# EEM_Connectors.net
KiCad netlist of a schematic drawn in Altium Designer
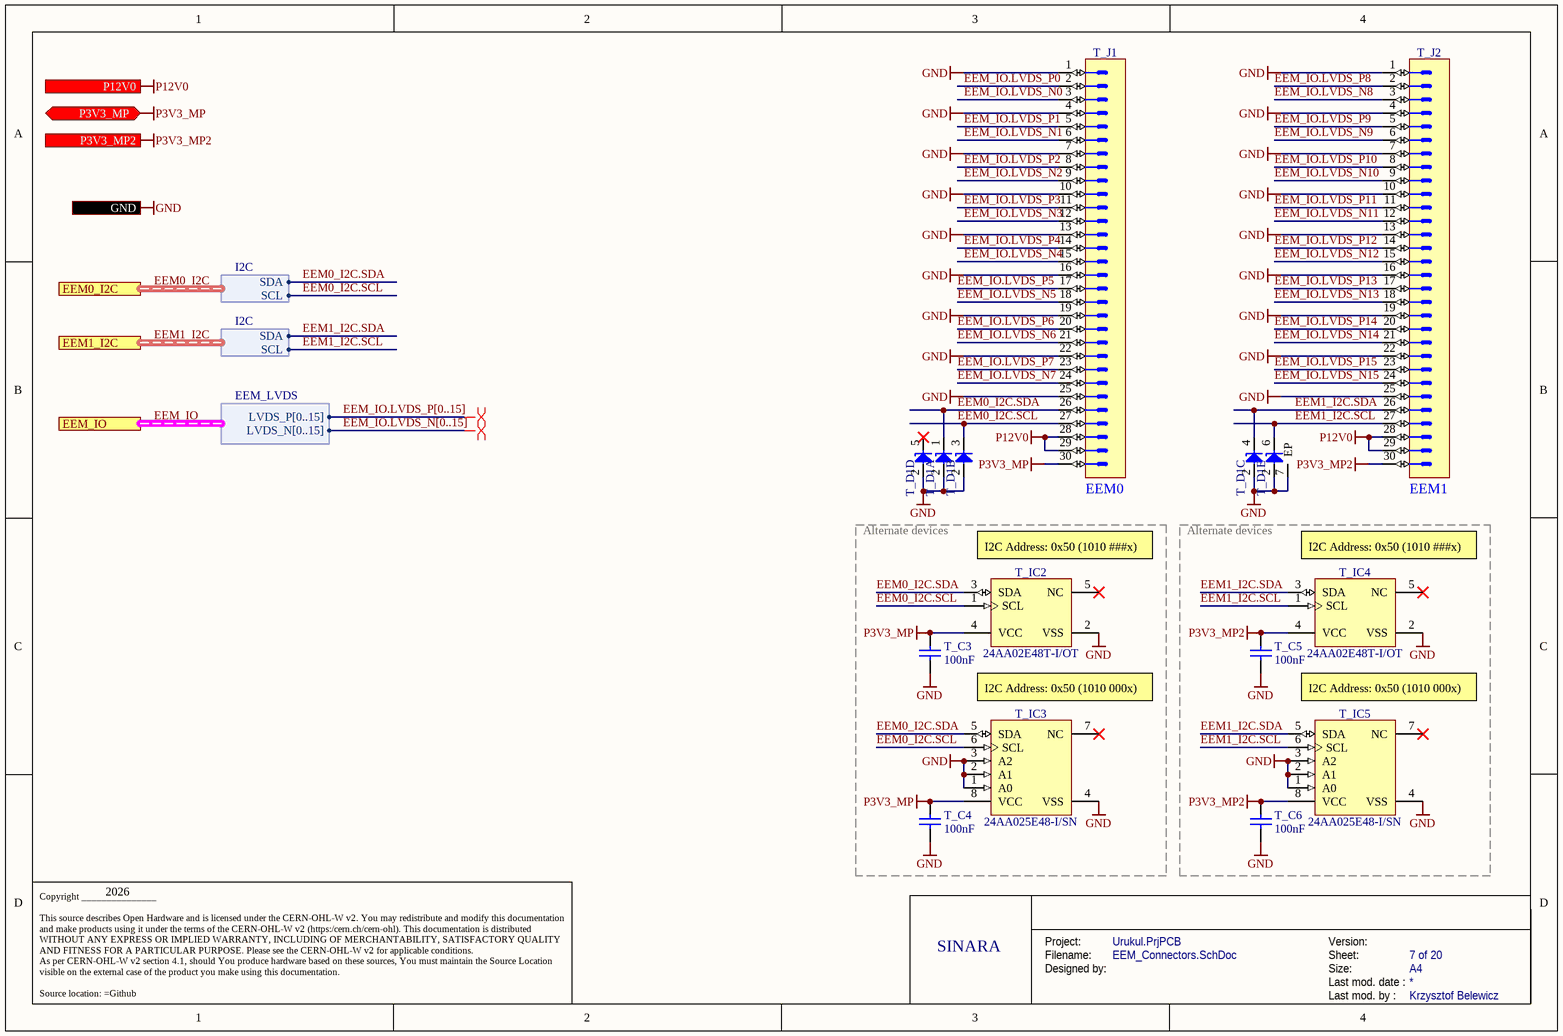
[diagram p0: EEM_Connectors.SchDoc]

(export (version "E")
  (design (tool "Eeschema 10.0.6"))
  (components
    (comp (ref "T_C3")
      (value "100nF")
      (footprint "CAPC1005X55N")
      (description "Non-polarised capacitor")
      (fields
        (field (name "PART NUMBER") "CC0402_100NF_16V_10%_X5R")
        (field (name "VOLTAGE") "16V")
        (field (name "AUTHOR") "CERN DEM JLC")
      )
      (libsource (lib "Capacitors") (part "Capacitor - non polarized"))
    )
    (comp (ref "T_C4")
      (value "100nF")
      (footprint "CAPC1005X55N")
      (description "Non-polarised capacitor")
      (fields
        (field (name "PART NUMBER") "CC0402_100NF_16V_10%_X5R")
        (field (name "VOLTAGE") "16V")
        (field (name "AUTHOR") "CERN DEM JLC")
      )
      (libsource (lib "Capacitors") (part "Capacitor - non polarized"))
    )
    (comp (ref "T_C5")
      (value "100nF")
      (footprint "CAPC1005X55N")
      (description "Non-polarised capacitor")
      (fields
        (field (name "PART NUMBER") "CC0402_100NF_16V_10%_X5R")
        (field (name "VOLTAGE") "16V")
        (field (name "AUTHOR") "CERN DEM JLC")
      )
      (libsource (lib "Capacitors") (part "Capacitor - non polarized"))
    )
    (comp (ref "T_C6")
      (value "100nF")
      (footprint "CAPC1005X55N")
      (description "Non-polarised capacitor")
      (fields
        (field (name "PART NUMBER") "CC0402_100NF_16V_10%_X5R")
        (field (name "VOLTAGE") "16V")
        (field (name "AUTHOR") "CERN DEM JLC")
      )
      (libsource (lib "Capacitors") (part "Capacitor - non polarized"))
    )
    (comp (ref "T_D1")
      (value "UCLAMP3305P.TCT")
      (footprint "SON50P160X65_HS-7N")
      (description "Diode TVS Quint Common Anode Uni-Dir 3.3V 40W 6-Pin SLP EP T/R")
      (libsource (lib "TechnoSystem Workspace") (part "D-AK-2"))
    )
    (comp (ref "T_IC2")
      (value "24AA02E48T-I/OT")
      (footprint "SOT95P280X145-5N")
      (description "1.7V-5.5V, 2K I2C Serial EEPROM With EUI-48 Node Identity")
      (fields (field (name "MANUFACTURER") "MICROCHIP TECHNOLOGY") (field (name "AUTHOR") "CERN DEM MR"))
      (libsource (lib "ICs And Semiconductors") (part "24AA02E48T-I/OT"))
    )
    (comp (ref "T_IC3")
      (value "24AA025E48-I/SN")
      (footprint "SOIC127P600X175-8N")
      (description "1.7V-5.5V, 2K I2C™ Serial EEPROMs with EUI-48™ Node Identity")
      (fields (field (name "MANUFACTURER") "MICROCHIP TECHNOLOGY") (field (name "AUTHOR") "CERN DEM MR"))
      (libsource (lib "ICs And Semiconductors") (part "24AA025E48-I/SN"))
    )
    (comp (ref "T_IC4")
      (value "24AA02E48T-I/OT")
      (footprint "SOT95P280X145-5N")
      (description "1.7V-5.5V, 2K I2C Serial EEPROM With EUI-48 Node Identity")
      (fields (field (name "MANUFACTURER") "MICROCHIP TECHNOLOGY") (field (name "AUTHOR") "CERN DEM MR"))
      (libsource (lib "ICs And Semiconductors") (part "24AA02E48T-I/OT"))
    )
    (comp (ref "T_IC5")
      (value "24AA025E48-I/SN")
      (footprint "SOIC127P600X175-8N")
      (description "1.7V-5.5V, 2K I2C™ Serial EEPROMs with EUI-48™ Node Identity")
      (fields (field (name "MANUFACTURER") "MICROCHIP TECHNOLOGY") (field (name "AUTHOR") "CERN DEM MR"))
      (libsource (lib "ICs And Semiconductors") (part "24AA025E48-I/SN"))
    )
    (comp (ref "T_J1")
      (value "~")
      (footprint "3M_N2530-6002RB")
      (description "Connector 30 Male")
      (fields
        (field (name "PART NUMBER") "3M_N2530-6002RB")
        (field (name "MANUFACTURER") "3M")
        (field (name "AUTHOR") "CERN DEM JLC")
      )
      (libsource (lib "Connectors") (part "Connector 30 Male"))
    )
    (comp (ref "T_J2")
      (value "~")
      (footprint "3M_N2530-6002RB")
      (description "Connector 30 Male")
      (fields
        (field (name "PART NUMBER") "3M_N2530-6002RB")
        (field (name "MANUFACTURER") "3M")
        (field (name "AUTHOR") "CERN DEM JLC")
      )
      (libsource (lib "Connectors") (part "Connector 30 Male"))
    )
  )
  (nets
    (net (code "4") (name "/EEM0_I2C.SCL") (class "Default")
      (node (ref "T_D1") (pin "3") (pinfunction "C_3") (pintype "passive"))
      (node (ref "T_IC2") (pin "1") (pinfunction "SCL_1") (pintype "input"))
      (node (ref "T_IC3") (pin "6") (pinfunction "SCL_6") (pintype "input"))
      (node (ref "T_J1") (pin "27") (pinfunction "27_27") (pintype "bidirectional"))
    )
    (net (code "5") (name "/EEM0_I2C.SDA") (class "Default")
      (node (ref "T_D1") (pin "1") (pinfunction "C_1") (pintype "passive"))
      (node (ref "T_IC2") (pin "3") (pinfunction "SDA_3") (pintype "bidirectional"))
      (node (ref "T_IC3") (pin "5") (pinfunction "SDA_5") (pintype "bidirectional"))
      (node (ref "T_J1") (pin "26") (pinfunction "26_26") (pintype "bidirectional"))
    )
    (net (code "7") (name "/EEM1_I2C.SCL") (class "Default")
      (node (ref "T_D1") (pin "6") (pinfunction "C_6") (pintype "passive"))
      (node (ref "T_IC4") (pin "1") (pinfunction "SCL_1") (pintype "input"))
      (node (ref "T_IC5") (pin "6") (pinfunction "SCL_6") (pintype "input"))
      (node (ref "T_J2") (pin "27") (pinfunction "27_27") (pintype "bidirectional"))
    )
    (net (code "8") (name "/EEM1_I2C.SDA") (class "Default")
      (node (ref "T_D1") (pin "4") (pinfunction "C_4") (pintype "passive"))
      (node (ref "T_IC4") (pin "3") (pinfunction "SDA_3") (pintype "bidirectional"))
      (node (ref "T_IC5") (pin "5") (pinfunction "SDA_5") (pintype "bidirectional"))
      (node (ref "T_J2") (pin "26") (pinfunction "26_26") (pintype "bidirectional"))
    )
    (net (code "10") (name "/EEM_IO.LVDS_N0") (class "Default")
      (node (ref "T_J1") (pin "3") (pinfunction "3_3") (pintype "bidirectional"))
    )
    (net (code "11") (name "/EEM_IO.LVDS_N1") (class "Default")
      (node (ref "T_J1") (pin "6") (pinfunction "6_6") (pintype "bidirectional"))
    )
    (net (code "12") (name "/EEM_IO.LVDS_N2") (class "Default")
      (node (ref "T_J1") (pin "9") (pinfunction "9_9") (pintype "bidirectional"))
    )
    (net (code "13") (name "/EEM_IO.LVDS_N3") (class "Default")
      (node (ref "T_J1") (pin "12") (pinfunction "12_12") (pintype "bidirectional"))
    )
    (net (code "14") (name "/EEM_IO.LVDS_N4") (class "Default")
      (node (ref "T_J1") (pin "15") (pinfunction "15_15") (pintype "bidirectional"))
    )
    (net (code "15") (name "/EEM_IO.LVDS_N5") (class "Default")
      (node (ref "T_J1") (pin "18") (pinfunction "18_18") (pintype "bidirectional"))
    )
    (net (code "16") (name "/EEM_IO.LVDS_N6") (class "Default")
      (node (ref "T_J1") (pin "21") (pinfunction "21_21") (pintype "bidirectional"))
    )
    (net (code "17") (name "/EEM_IO.LVDS_N7") (class "Default")
      (node (ref "T_J1") (pin "24") (pinfunction "24_24") (pintype "bidirectional"))
    )
    (net (code "18") (name "/EEM_IO.LVDS_N8") (class "Default")
      (node (ref "T_J2") (pin "3") (pinfunction "3_3") (pintype "bidirectional"))
    )
    (net (code "19") (name "/EEM_IO.LVDS_N9") (class "Default")
      (node (ref "T_J2") (pin "6") (pinfunction "6_6") (pintype "bidirectional"))
    )
    (net (code "20") (name "/EEM_IO.LVDS_N10") (class "Default")
      (node (ref "T_J2") (pin "9") (pinfunction "9_9") (pintype "bidirectional"))
    )
    (net (code "21") (name "/EEM_IO.LVDS_N11") (class "Default")
      (node (ref "T_J2") (pin "12") (pinfunction "12_12") (pintype "bidirectional"))
    )
    (net (code "22") (name "/EEM_IO.LVDS_N12") (class "Default")
      (node (ref "T_J2") (pin "15") (pinfunction "15_15") (pintype "bidirectional"))
    )
    (net (code "23") (name "/EEM_IO.LVDS_N13") (class "Default")
      (node (ref "T_J2") (pin "18") (pinfunction "18_18") (pintype "bidirectional"))
    )
    (net (code "24") (name "/EEM_IO.LVDS_N14") (class "Default")
      (node (ref "T_J2") (pin "21") (pinfunction "21_21") (pintype "bidirectional"))
    )
    (net (code "25") (name "/EEM_IO.LVDS_N15") (class "Default")
      (node (ref "T_J2") (pin "24") (pinfunction "24_24") (pintype "bidirectional"))
    )
    (net (code "27") (name "/EEM_IO.LVDS_P0") (class "Default")
      (node (ref "T_J1") (pin "2") (pinfunction "2_2") (pintype "bidirectional"))
    )
    (net (code "28") (name "/EEM_IO.LVDS_P1") (class "Default")
      (node (ref "T_J1") (pin "5") (pinfunction "5_5") (pintype "bidirectional"))
    )
    (net (code "29") (name "/EEM_IO.LVDS_P2") (class "Default")
      (node (ref "T_J1") (pin "8") (pinfunction "8_8") (pintype "bidirectional"))
    )
    (net (code "30") (name "/EEM_IO.LVDS_P3") (class "Default")
      (node (ref "T_J1") (pin "11") (pinfunction "11_11") (pintype "bidirectional"))
    )
    (net (code "31") (name "/EEM_IO.LVDS_P4") (class "Default")
      (node (ref "T_J1") (pin "14") (pinfunction "14_14") (pintype "bidirectional"))
    )
    (net (code "32") (name "/EEM_IO.LVDS_P5") (class "Default")
      (node (ref "T_J1") (pin "17") (pinfunction "17_17") (pintype "bidirectional"))
    )
    (net (code "33") (name "/EEM_IO.LVDS_P6") (class "Default")
      (node (ref "T_J1") (pin "20") (pinfunction "20_20") (pintype "bidirectional"))
    )
    (net (code "34") (name "/EEM_IO.LVDS_P7") (class "Default")
      (node (ref "T_J1") (pin "23") (pinfunction "23_23") (pintype "bidirectional"))
    )
    (net (code "35") (name "/EEM_IO.LVDS_P8") (class "Default")
      (node (ref "T_J2") (pin "2") (pinfunction "2_2") (pintype "bidirectional"))
    )
    (net (code "36") (name "/EEM_IO.LVDS_P9") (class "Default")
      (node (ref "T_J2") (pin "5") (pinfunction "5_5") (pintype "bidirectional"))
    )
    (net (code "37") (name "/EEM_IO.LVDS_P10") (class "Default")
      (node (ref "T_J2") (pin "8") (pinfunction "8_8") (pintype "bidirectional"))
    )
    (net (code "38") (name "/EEM_IO.LVDS_P11") (class "Default")
      (node (ref "T_J2") (pin "11") (pinfunction "11_11") (pintype "bidirectional"))
    )
    (net (code "39") (name "/EEM_IO.LVDS_P12") (class "Default")
      (node (ref "T_J2") (pin "14") (pinfunction "14_14") (pintype "bidirectional"))
    )
    (net (code "40") (name "/EEM_IO.LVDS_P13") (class "Default")
      (node (ref "T_J2") (pin "17") (pinfunction "17_17") (pintype "bidirectional"))
    )
    (net (code "41") (name "/EEM_IO.LVDS_P14") (class "Default")
      (node (ref "T_J2") (pin "20") (pinfunction "20_20") (pintype "bidirectional"))
    )
    (net (code "42") (name "/EEM_IO.LVDS_P15") (class "Default")
      (node (ref "T_J2") (pin "23") (pinfunction "23_23") (pintype "bidirectional"))
    )
    (net (code "45") (name "GND") (class "Default")
      (node (ref "T_C3") (pin "1") (pinfunction "1_1") (pintype "passive"))
      (node (ref "T_C4") (pin "1") (pinfunction "1_1") (pintype "passive"))
      (node (ref "T_C5") (pin "1") (pinfunction "1_1") (pintype "passive"))
      (node (ref "T_C6") (pin "1") (pinfunction "1_1") (pintype "passive"))
      (node (ref "T_D1") (pin "2") (pinfunction "A_2") (pintype "passive"))
      (node (ref "T_D1") (pin "7") (pinfunction "EP_7") (pintype "passive"))
      (node (ref "T_IC2") (pin "2") (pinfunction "VSS_2") (pintype "power_in"))
      (node (ref "T_IC3") (pin "1") (pinfunction "A0_1") (pintype "input"))
      (node (ref "T_IC3") (pin "2") (pinfunction "A1_2") (pintype "input"))
      (node (ref "T_IC3") (pin "3") (pinfunction "A2_3") (pintype "input"))
      (node (ref "T_IC3") (pin "4") (pinfunction "VSS_4") (pintype "power_in"))
      (node (ref "T_IC4") (pin "2") (pinfunction "VSS_2") (pintype "power_in"))
      (node (ref "T_IC5") (pin "1") (pinfunction "A0_1") (pintype "input"))
      (node (ref "T_IC5") (pin "2") (pinfunction "A1_2") (pintype "input"))
      (node (ref "T_IC5") (pin "3") (pinfunction "A2_3") (pintype "input"))
      (node (ref "T_IC5") (pin "4") (pinfunction "VSS_4") (pintype "power_in"))
      (node (ref "T_J1") (pin "1") (pinfunction "1_1") (pintype "bidirectional"))
      (node (ref "T_J1") (pin "10") (pinfunction "10_10") (pintype "bidirectional"))
      (node (ref "T_J1") (pin "13") (pinfunction "13_13") (pintype "bidirectional"))
      (node (ref "T_J1") (pin "16") (pinfunction "16_16") (pintype "bidirectional"))
      (node (ref "T_J1") (pin "19") (pinfunction "19_19") (pintype "bidirectional"))
      (node (ref "T_J1") (pin "22") (pinfunction "22_22") (pintype "bidirectional"))
      (node (ref "T_J1") (pin "25") (pinfunction "25_25") (pintype "bidirectional"))
      (node (ref "T_J1") (pin "4") (pinfunction "4_4") (pintype "bidirectional"))
      (node (ref "T_J1") (pin "7") (pinfunction "7_7") (pintype "bidirectional"))
      (node (ref "T_J2") (pin "1") (pinfunction "1_1") (pintype "bidirectional"))
      (node (ref "T_J2") (pin "10") (pinfunction "10_10") (pintype "bidirectional"))
      (node (ref "T_J2") (pin "13") (pinfunction "13_13") (pintype "bidirectional"))
      (node (ref "T_J2") (pin "16") (pinfunction "16_16") (pintype "bidirectional"))
      (node (ref "T_J2") (pin "19") (pinfunction "19_19") (pintype "bidirectional"))
      (node (ref "T_J2") (pin "22") (pinfunction "22_22") (pintype "bidirectional"))
      (node (ref "T_J2") (pin "25") (pinfunction "25_25") (pintype "bidirectional"))
      (node (ref "T_J2") (pin "4") (pinfunction "4_4") (pintype "bidirectional"))
      (node (ref "T_J2") (pin "7") (pinfunction "7_7") (pintype "bidirectional"))
    )
    (net (code "46") (name "P3V3_MP") (class "Default")
      (node (ref "T_C3") (pin "2") (pinfunction "2_2") (pintype "passive"))
      (node (ref "T_C4") (pin "2") (pinfunction "2_2") (pintype "passive"))
      (node (ref "T_IC2") (pin "4") (pinfunction "VCC_4") (pintype "power_in"))
      (node (ref "T_IC3") (pin "8") (pinfunction "VCC_8") (pintype "power_in"))
      (node (ref "T_J1") (pin "30") (pinfunction "30_30") (pintype "bidirectional"))
    )
    (net (code "47") (name "P3V3_MP2") (class "Default")
      (node (ref "T_C5") (pin "2") (pinfunction "2_2") (pintype "passive"))
      (node (ref "T_C6") (pin "2") (pinfunction "2_2") (pintype "passive"))
      (node (ref "T_IC4") (pin "4") (pinfunction "VCC_4") (pintype "power_in"))
      (node (ref "T_IC5") (pin "8") (pinfunction "VCC_8") (pintype "power_in"))
      (node (ref "T_J2") (pin "30") (pinfunction "30_30") (pintype "bidirectional"))
    )
    (net (code "48") (name "P12V0") (class "Default")
      (node (ref "T_J1") (pin "28") (pinfunction "28_28") (pintype "bidirectional"))
      (node (ref "T_J1") (pin "29") (pinfunction "29_29") (pintype "bidirectional"))
      (node (ref "T_J2") (pin "28") (pinfunction "28_28") (pintype "bidirectional"))
      (node (ref "T_J2") (pin "29") (pinfunction "29_29") (pintype "bidirectional"))
    )
    (net (code "49") (name "unconnected-(T_D1D-C-Pad5)") (class "Default")
      (node (ref "T_D1") (pin "5") (pinfunction "C_5") (pintype "passive+no_connect"))
    )
    (net (code "50") (name "unconnected-(T_IC2-NC-Pad5)") (class "Default")
      (node (ref "T_IC2") (pin "5") (pinfunction "NC_5") (pintype "passive+no_connect"))
    )
    (net (code "51") (name "unconnected-(T_IC3-NC-Pad7)") (class "Default")
      (node (ref "T_IC3") (pin "7") (pinfunction "NC_7") (pintype "passive+no_connect"))
    )
    (net (code "52") (name "unconnected-(T_IC4-NC-Pad5)") (class "Default")
      (node (ref "T_IC4") (pin "5") (pinfunction "NC_5") (pintype "passive+no_connect"))
    )
    (net (code "53") (name "unconnected-(T_IC5-NC-Pad7)") (class "Default")
      (node (ref "T_IC5") (pin "7") (pinfunction "NC_7") (pintype "passive+no_connect"))
    )
  )
)
